# gunboard.net
KiCad netlist of a schematic drawn in EAGLE
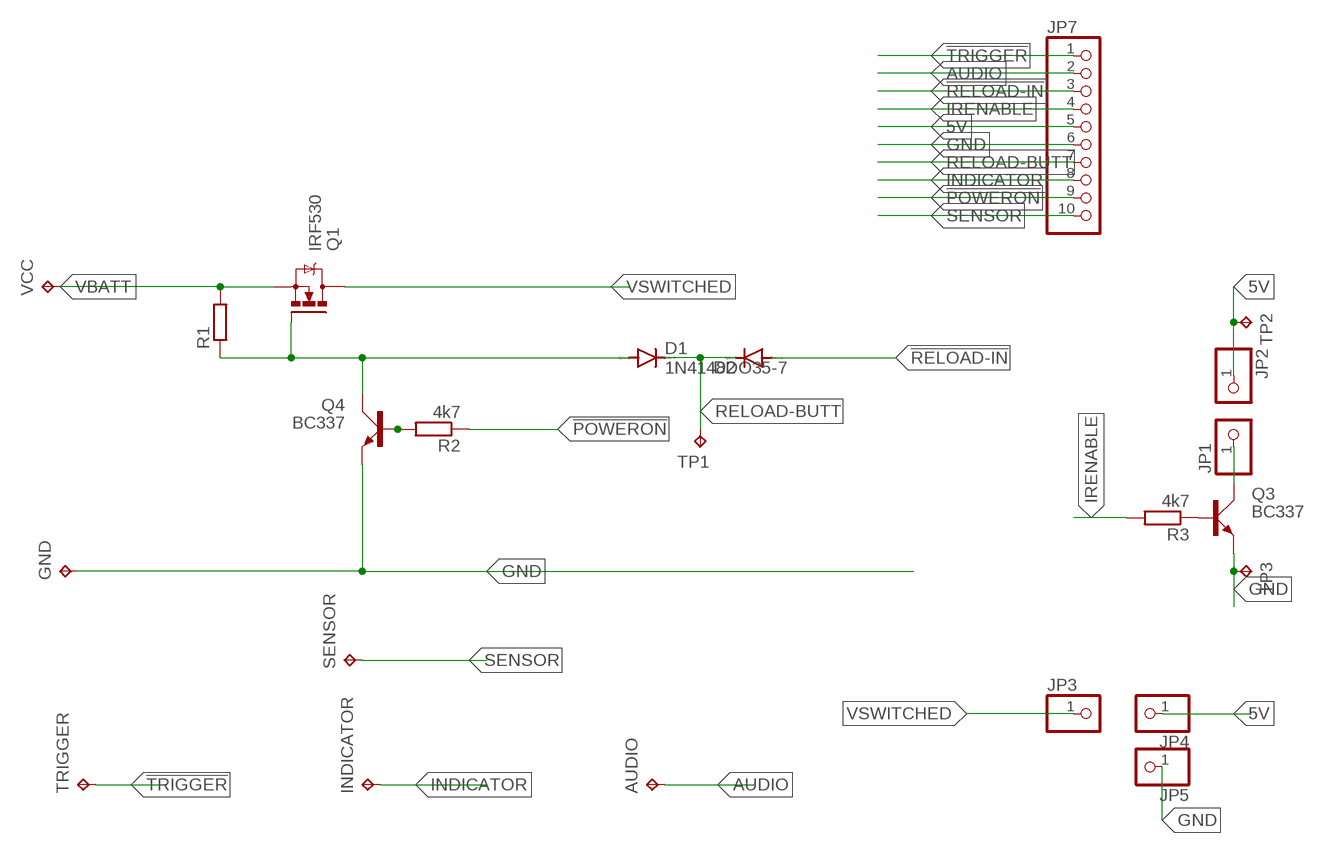
[diagram p0: schematic, sheet 1]

(export (version "E")
  (design (tool "Eeschema 10.0.6"))
  (components
    (comp (ref "AUDIO")
      (value "TPTP20SQ")
      (footprint "eagle-import:TP20SQ")
      (libsource (lib "eagle-import") (part "TPTP20SQ"))
    )
    (comp (ref "D1")
      (value "1N4148DO35-7")
      (footprint "eagle-import:DO35-7")
      (libsource (lib "eagle-import") (part "1N4148DO35-7"))
    )
    (comp (ref "D2")
      (value "DIODE-DO35-10")
      (footprint "eagle-import:DO35-10")
      (libsource (lib "eagle-import") (part "DIODE-DO35-10"))
    )
    (comp (ref "GND")
      (value "TPTP20SQ")
      (footprint "eagle-import:TP20SQ")
      (libsource (lib "eagle-import") (part "TPTP20SQ"))
    )
    (comp (ref "INDICATOR")
      (value "TPTP20SQ")
      (footprint "eagle-import:TP20SQ")
      (libsource (lib "eagle-import") (part "TPTP20SQ"))
    )
    (comp (ref "JP1")
      (value "PINHD-1X1")
      (footprint "eagle-import:1X01")
      (libsource (lib "eagle-import") (part "PINHD-1X1"))
    )
    (comp (ref "JP2")
      (value "PINHD-1X1")
      (footprint "eagle-import:1X01")
      (libsource (lib "eagle-import") (part "PINHD-1X1"))
    )
    (comp (ref "JP3")
      (value "PINHD-1X1")
      (footprint "eagle-import:1X01")
      (libsource (lib "eagle-import") (part "PINHD-1X1"))
    )
    (comp (ref "JP4")
      (value "PINHD-1X1")
      (footprint "eagle-import:1X01")
      (libsource (lib "eagle-import") (part "PINHD-1X1"))
    )
    (comp (ref "JP5")
      (value "PINHD-1X1")
      (footprint "eagle-import:1X01")
      (libsource (lib "eagle-import") (part "PINHD-1X1"))
    )
    (comp (ref "JP7")
      (value "PINHD-1X10")
      (footprint "eagle-import:1X10")
      (libsource (lib "eagle-import") (part "PINHD-1X10"))
    )
    (comp (ref "Q1")
      (value "IRF530")
      (footprint "eagle-import:TO220BV")
      (libsource (lib "eagle-import") (part "IRF530"))
    )
    (comp (ref "Q3")
      (value "BC337")
      (footprint "eagle-import:SOT54A")
      (libsource (lib "eagle-import") (part "BC337"))
    )
    (comp (ref "Q4")
      (value "BC337")
      (footprint "eagle-import:SOT54A")
      (libsource (lib "eagle-import") (part "BC337"))
    )
    (comp (ref "R1")
      (value "R-EU_0207/5V")
      (footprint "eagle-import:0207_5V")
      (libsource (lib "eagle-import") (part "R-EU_0207/5V"))
    )
    (comp (ref "R2")
      (value "4k7")
      (footprint "eagle-import:0207_10")
      (libsource (lib "eagle-import") (part "R-EU_0207/10"))
    )
    (comp (ref "R3")
      (value "4k7")
      (footprint "eagle-import:0207_10")
      (libsource (lib "eagle-import") (part "R-EU_0207/10"))
    )
    (comp (ref "SENSOR")
      (value "TPTP20SQ")
      (footprint "eagle-import:TP20SQ")
      (libsource (lib "eagle-import") (part "TPTP20SQ"))
    )
    (comp (ref "TP1")
      (value "TPTP20SQ")
      (footprint "eagle-import:TP20SQ")
      (libsource (lib "eagle-import") (part "TPTP20SQ"))
    )
    (comp (ref "TP2")
      (value "TPTP20SQ")
      (footprint "eagle-import:TP20SQ")
      (libsource (lib "eagle-import") (part "TPTP20SQ"))
    )
    (comp (ref "TP3")
      (value "TPTP20SQ")
      (footprint "eagle-import:TP20SQ")
      (libsource (lib "eagle-import") (part "TPTP20SQ"))
    )
    (comp (ref "TRIGGER")
      (value "TPTP20SQ")
      (footprint "eagle-import:TP20SQ")
      (libsource (lib "eagle-import") (part "TPTP20SQ"))
    )
    (comp (ref "VCC")
      (value "TPTP20SQ")
      (footprint "eagle-import:TP20SQ")
      (libsource (lib "eagle-import") (part "TPTP20SQ"))
    )
  )
  (nets
    (net (code "1") (name "/~{POWERON}") (class "Default")
      (node (ref "JP7") (pin "9") (pinfunction "9_9") (pintype "passive"))
      (node (ref "R2") (pin "1") (pinfunction "1_1") (pintype "passive"))
    )
    (net (code "2") (name "/~{RELOAD-IN}") (class "Default")
      (node (ref "D2") (pin "A") (pinfunction "A_A") (pintype "passive"))
      (node (ref "JP7") (pin "3") (pinfunction "3_3") (pintype "passive"))
    )
    (net (code "3") (name "/~{TRIGGER}") (class "Default")
      (node (ref "JP7") (pin "1") (pinfunction "1_1") (pintype "passive"))
      (node (ref "TRIGGER") (pin "TP") (pinfunction "TP_TP") (pintype "input"))
    )
    (net (code "4") (name "5V") (class "Default")
      (node (ref "JP2") (pin "1") (pinfunction "1_1") (pintype "passive"))
      (node (ref "JP4") (pin "1") (pinfunction "1_1") (pintype "passive"))
      (node (ref "JP7") (pin "5") (pinfunction "5_5") (pintype "passive"))
      (node (ref "TP2") (pin "TP") (pinfunction "TP_TP") (pintype "input"))
    )
    (net (code "5") (name "AUDIO") (class "Default")
      (node (ref "AUDIO") (pin "TP") (pinfunction "TP_TP") (pintype "input"))
      (node (ref "JP7") (pin "2") (pinfunction "2_2") (pintype "passive"))
    )
    (net (code "6") (name "GND") (class "Default")
      (node (ref "GND") (pin "TP") (pinfunction "TP_TP") (pintype "input"))
      (node (ref "JP5") (pin "1") (pinfunction "1_1") (pintype "passive"))
      (node (ref "JP7") (pin "6") (pinfunction "6_6") (pintype "passive"))
      (node (ref "Q3") (pin "E") (pinfunction "E_E") (pintype "passive"))
      (node (ref "Q4") (pin "E") (pinfunction "E_E") (pintype "passive"))
      (node (ref "TP3") (pin "TP") (pinfunction "TP_TP") (pintype "input"))
    )
    (net (code "7") (name "INDICATOR") (class "Default")
      (node (ref "INDICATOR") (pin "TP") (pinfunction "TP_TP") (pintype "input"))
      (node (ref "JP7") (pin "8") (pinfunction "8_8") (pintype "passive"))
    )
    (net (code "8") (name "IRENABLE") (class "Default")
      (node (ref "JP7") (pin "4") (pinfunction "4_4") (pintype "passive"))
      (node (ref "R3") (pin "2") (pinfunction "2_2") (pintype "passive"))
    )
    (net (code "9") (name "Net-(D1-PadA)") (class "Default")
      (node (ref "D1") (pin "A") (pinfunction "A_A") (pintype "passive"))
      (node (ref "Q1") (pin "G") (pinfunction "G_G") (pintype "passive"))
      (node (ref "Q4") (pin "C") (pinfunction "C_C") (pintype "passive"))
      (node (ref "R1") (pin "1") (pinfunction "1_1") (pintype "passive"))
    )
    (net (code "10") (name "Net-(JP1-Pad1)") (class "Default")
      (node (ref "JP1") (pin "1") (pinfunction "1_1") (pintype "passive"))
      (node (ref "Q3") (pin "C") (pinfunction "C_C") (pintype "passive"))
    )
    (net (code "11") (name "Net-(Q3-PadB)") (class "Default")
      (node (ref "Q3") (pin "B") (pinfunction "B_B") (pintype "passive"))
      (node (ref "R3") (pin "1") (pinfunction "1_1") (pintype "passive"))
    )
    (net (code "12") (name "Net-(Q4-PadB)") (class "Default")
      (node (ref "Q4") (pin "B") (pinfunction "B_B") (pintype "passive"))
      (node (ref "R2") (pin "2") (pinfunction "2_2") (pintype "passive"))
    )
    (net (code "13") (name "RELOAD-BUTT") (class "Default")
      (node (ref "D1") (pin "C") (pinfunction "C_C") (pintype "passive"))
      (node (ref "D2") (pin "C") (pinfunction "C_C") (pintype "passive"))
      (node (ref "JP7") (pin "7") (pinfunction "7_7") (pintype "passive"))
      (node (ref "TP1") (pin "TP") (pinfunction "TP_TP") (pintype "input"))
    )
    (net (code "14") (name "SENSOR") (class "Default")
      (node (ref "JP7") (pin "10") (pinfunction "10_10") (pintype "passive"))
      (node (ref "SENSOR") (pin "TP") (pinfunction "TP_TP") (pintype "input"))
    )
    (net (code "15") (name "VBATT") (class "Default")
      (node (ref "Q1") (pin "S") (pinfunction "S_S") (pintype "passive"))
      (node (ref "R1") (pin "2") (pinfunction "2_2") (pintype "passive"))
      (node (ref "VCC") (pin "TP") (pinfunction "TP_TP") (pintype "input"))
    )
    (net (code "16") (name "VSWITCHED") (class "Default")
      (node (ref "JP3") (pin "1") (pinfunction "1_1") (pintype "passive"))
      (node (ref "Q1") (pin "D") (pinfunction "D_D") (pintype "passive"))
    )
  )
)
